# DS144-1_0-B.net
KiCad netlist of a schematic drawn in Altium Designer
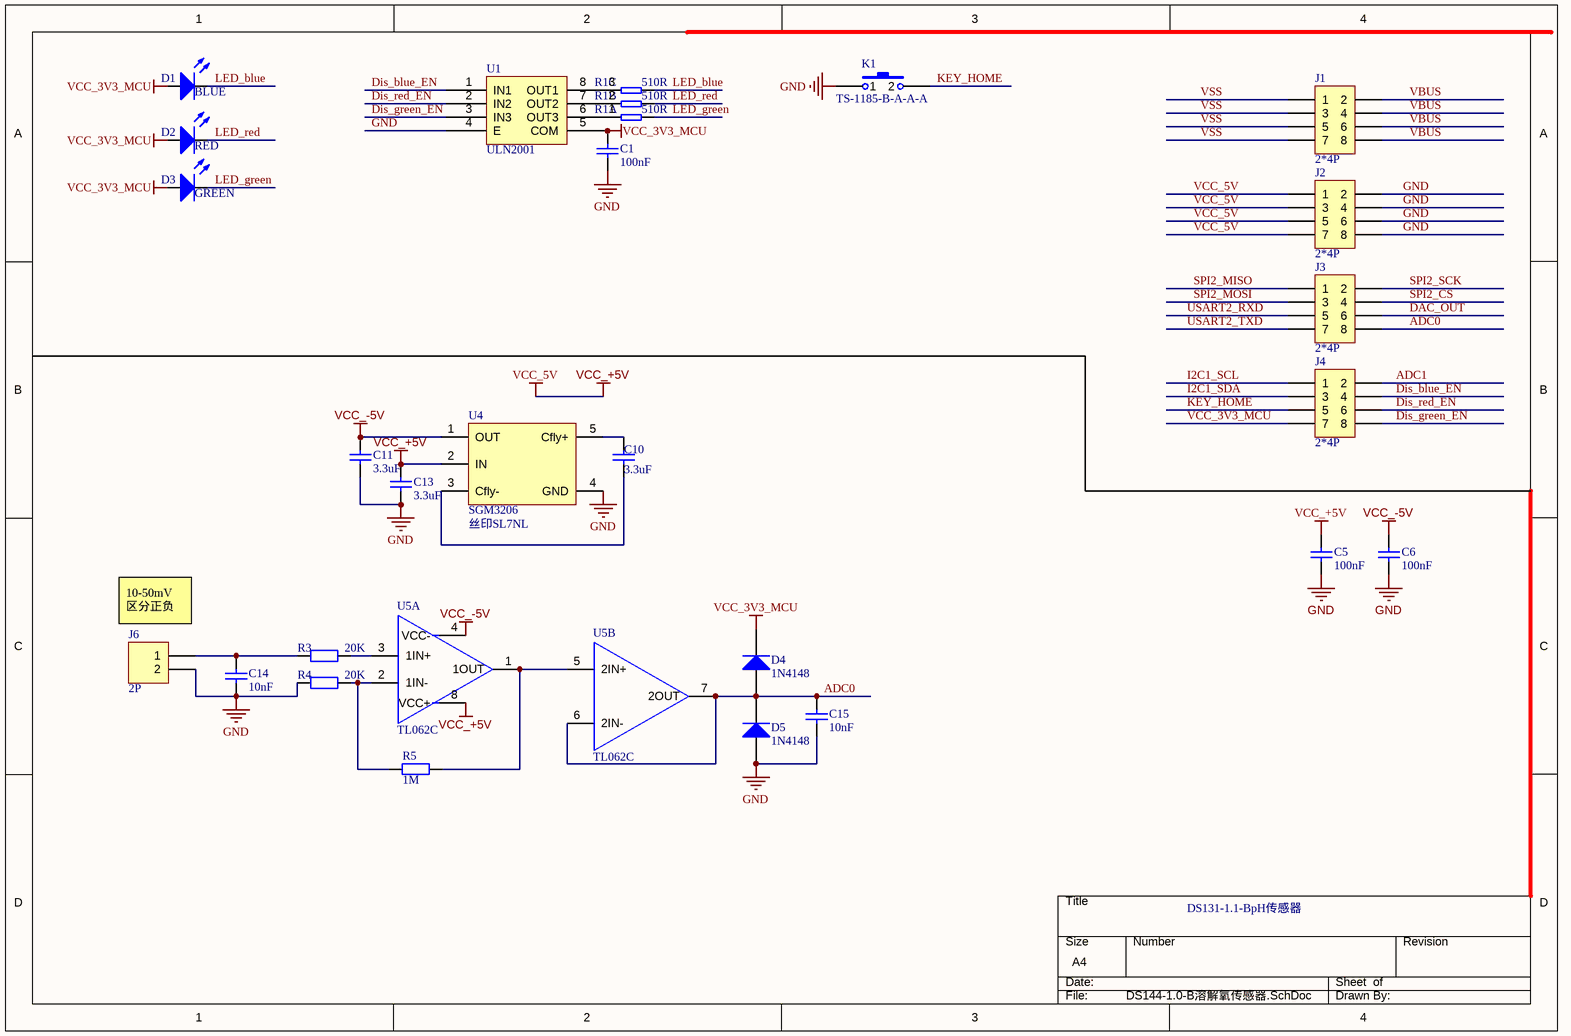
[diagram p0: DS144-1.0-B溶解氧传感器.SchDoc]

(export (version "E")
  (design (tool "Eeschema 10.0.6"))
  (components
    (comp (ref "C1")
      (value "100nF")
      (footprint "0603CAP")
      (description "贴片电容")
      (fields (field (name "Comment") "SMDCAP00013"))
      (libsource (lib "AD_SCH") (part "MLCC 100nF 50V ±10％ 0603"))
    )
    (comp (ref "C5")
      (value "100nF")
      (footprint "0603CAP")
      (description "贴片电容")
      (fields (field (name "Comment") "SMDCAP00013"))
      (libsource (lib "AD_SCH") (part "MLCC 100nF 50V ±10％ 0603"))
    )
    (comp (ref "C6")
      (value "100nF")
      (footprint "0603CAP")
      (description "贴片电容")
      (fields (field (name "Comment") "SMDCAP00013"))
      (libsource (lib "AD_SCH") (part "MLCC 100nF 50V ±10％ 0603"))
    )
    (comp (ref "C10")
      (value "3.3uF")
      (footprint "0603CAP")
      (description "贴片电容")
      (fields (field (name "Comment") "SMDCAP00016"))
      (libsource (lib "AD_SCH") (part "MLCC 10uF 50V ±10％ 0603"))
    )
    (comp (ref "C11")
      (value "3.3uF")
      (footprint "0603CAP")
      (description "贴片电容")
      (fields (field (name "Comment") "SMDCAP00016"))
      (libsource (lib "AD_SCH") (part "MLCC 10uF 50V ±10％ 0603"))
    )
    (comp (ref "C13")
      (value "3.3uF")
      (footprint "0603CAP")
      (description "贴片电容")
      (fields (field (name "Comment") "SMDCAP00016"))
      (libsource (lib "AD_SCH") (part "MLCC 10uF 50V ±10％ 0603"))
    )
    (comp (ref "C14")
      (value "10nF")
      (footprint "0603CAP")
      (description "贴片电容")
      (fields (field (name "Comment") "SMDCAP00010"))
      (libsource (lib "AD_SCH") (part "MLCC 10nF 50V ±10％ 0603"))
    )
    (comp (ref "C15")
      (value "10nF")
      (footprint "0603CAP")
      (description "贴片电容")
      (fields (field (name "Comment") "SMDCAP00010"))
      (libsource (lib "AD_SCH") (part "MLCC 10nF 50V ±10％ 0603"))
    )
    (comp (ref "D1")
      (value "BLUE")
      (footprint "LED_0805")
      (description "贴片LED")
      (fields (field (name "Comment") "SMDLED00010"))
      (libsource (lib "AD_SCH") (part "Chip 蓝色LED 0805"))
    )
    (comp (ref "D2")
      (value "RED")
      (footprint "LED_0805")
      (description "贴片LED")
      (fields (field (name "Comment") "SMDLED00003"))
      (libsource (lib "AD_SCH") (part "Chip 红色LED 0805"))
    )
    (comp (ref "D3")
      (value "GREEN")
      (footprint "LED_0805")
      (description "贴片LED")
      (fields (field (name "Comment") "Chip 翠绿LED 0805"))
      (libsource (lib "AD_SCH") (part "Chip 翠绿LED 0805"))
    )
    (comp (ref "D4")
      (value "1N4148")
      (footprint "SOD-123")
      (description "贴片开关二极管 T4")
      (fields (field (name "Comment") "DIPDIODE02001"))
      (libsource (lib "AD_SCH") (part "1N4148W"))
    )
    (comp (ref "D5")
      (value "1N4148")
      (footprint "SOD-123")
      (description "贴片开关二极管 T4")
      (fields (field (name "Comment") "DIPDIODE02001"))
      (libsource (lib "AD_SCH") (part "1N4148W"))
    )
    (comp (ref "J1")
      (value "2*4P")
      (footprint "X1321WVS-2x04J-C40D53")
      (description "双排针2x4P 立贴 1.27mm")
      (fields (field (name "Comment") "X1321WVS-2x04J-C40D53"))
      (libsource (lib "AD_SCH") (part "X1321WVS-2x04J-C40D53"))
    )
    (comp (ref "J2")
      (value "2*4P")
      (footprint "X1321WVS-2x04J-C40D53")
      (description "双排针2x4P 立贴 1.27mm")
      (fields (field (name "Comment") "X1321WVS-2x04J-C40D53"))
      (libsource (lib "AD_SCH") (part "X1321WVS-2x04J-C40D53"))
    )
    (comp (ref "J3")
      (value "2*4P")
      (footprint "X1321WVS-2x04J-C40D53")
      (description "双排针2x4P 立贴 1.27mm")
      (fields (field (name "Comment") "X1321WVS-2x04J-C40D53"))
      (libsource (lib "AD_SCH") (part "X1321WVS-2x04J-C40D53"))
    )
    (comp (ref "J4")
      (value "2*4P")
      (footprint "X1321WVS-2x04J-C40D53")
      (description "双排针2x4P 立贴 1.27mm")
      (fields (field (name "Comment") "X1321WVS-2x04J-C40D53"))
      (libsource (lib "AD_SCH") (part "X1321WVS-2x04J-C40D53"))
    )
    (comp (ref "J6")
      (value "2P")
      (footprint "SIP2")
      (description "单排直针")
      (fields (field (name "Comment") "SL000000042"))
      (libsource (lib "AD_SCH") (part "DIP2 单排直针 1*40P 间距2.54mm 针长11mm 铜"))
    )
    (comp (ref "K1")
      (value "TS-1185-B-A-A-A")
      (footprint "KEY_TS-1185-x-A-A-A")
      (description "轻触开关")
      (libsource (lib "AD_SCH") (part "TS-1185-B-A-A-A"))
    )
    (comp (ref "R1")
      (value "510R")
      (footprint "0603RES_Pack4")
      (description "贴片排阻")
      (fields (field (name "Comment") "SMDRES05003"))
      (libsource (lib "AD_SCH") (part "Chip R*4 510R 1/16W ±5％ 0603"))
    )
    (comp (ref "R3")
      (value "20K")
      (footprint "0603RES")
      (description "贴片电阻")
      (fields (field (name "Comment") "SMDRES00058"))
      (libsource (lib "") (part "Chip 20K 1/16W ±1％ 0603_1"))
    )
    (comp (ref "R4")
      (value "20K")
      (footprint "0603RES")
      (description "贴片电阻")
      (fields (field (name "Comment") "SMDRES00058"))
      (libsource (lib "AD_SCH") (part "Chip 20K 1/16W ±1％ 0603"))
    )
    (comp (ref "R5")
      (value "1M")
      (footprint "0603RES")
      (description "贴片电阻")
      (fields (field (name "Comment") "SMDRES00085"))
      (libsource (lib "AD_SCH") (part "Chip 1M 1/16W ±1％ 0603"))
    )
    (comp (ref "U1")
      (value "ULN2001")
      (footprint "SO-8")
      (description "电机驱动芯片")
      (fields (field (name "Comment") "SMDIC000018"))
      (libsource (lib "AD_SCH") (part "ULN2001 SOP-8"))
    )
    (comp (ref "U4")
      (value "SGM3206")
      (footprint "SOT23-5")
      (description "电荷泵芯片")
      (fields (field (name "ALTIUM_VALUE") "丝印SL7NL"))
      (libsource (lib "AD_SCH") (part "SGM3206"))
    )
    (comp (ref "U5") (value "TL062C") (footprint "SO-8") (libsource (lib "AD_SCH") (part "TL062C")))
  )
  (nets
    (net (code "1") (name "/ADC0") (class "Default")
      (node (ref "C15") (pin "2") (pinfunction "2_2") (pintype "passive"))
      (node (ref "D4") (pin "1") (pinfunction "A_1") (pintype "passive"))
      (node (ref "D5") (pin "2") (pinfunction "K_2") (pintype "passive"))
      (node (ref "J3") (pin "8") (pinfunction "8_8") (pintype "passive"))
      (node (ref "U5") (pin "6") (pinfunction "2IN-_6") (pintype "passive"))
      (node (ref "U5") (pin "7") (pinfunction "2OUT_7") (pintype "passive"))
    )
    (net (code "2") (name "/ADC1") (class "Default")
      (node (ref "J4") (pin "2") (pinfunction "2_2") (pintype "passive"))
    )
    (net (code "3") (name "/DAC_OUT") (class "Default")
      (node (ref "J3") (pin "6") (pinfunction "6_6") (pintype "passive"))
    )
    (net (code "4") (name "/Dis_blue_EN") (class "Default")
      (node (ref "J4") (pin "4") (pinfunction "4_4") (pintype "passive"))
      (node (ref "U1") (pin "1") (pinfunction "IN1_1") (pintype "passive"))
    )
    (net (code "5") (name "/Dis_green_EN") (class "Default")
      (node (ref "J4") (pin "8") (pinfunction "8_8") (pintype "passive"))
      (node (ref "U1") (pin "3") (pinfunction "IN3_3") (pintype "passive"))
    )
    (net (code "6") (name "/Dis_red_EN") (class "Default")
      (node (ref "J4") (pin "6") (pinfunction "6_6") (pintype "passive"))
      (node (ref "U1") (pin "2") (pinfunction "IN2_2") (pintype "passive"))
    )
    (net (code "7") (name "/I2C1_SCL") (class "Default")
      (node (ref "J4") (pin "1") (pinfunction "1_1") (pintype "passive"))
    )
    (net (code "8") (name "/I2C1_SDA") (class "Default")
      (node (ref "J4") (pin "3") (pinfunction "3_3") (pintype "passive"))
    )
    (net (code "9") (name "/KEY_HOME") (class "Default")
      (node (ref "J4") (pin "5") (pinfunction "5_5") (pintype "passive"))
      (node (ref "K1") (pin "2") (pinfunction "2_2") (pintype "passive"))
    )
    (net (code "10") (name "/LED_blue") (class "Default")
      (node (ref "D1") (pin "2") (pinfunction "K_2") (pintype "passive"))
      (node (ref "R1") (pin "6") (pinfunction "6_6") (pintype "passive"))
    )
    (net (code "11") (name "/LED_green") (class "Default")
      (node (ref "D3") (pin "2") (pinfunction "K_2") (pintype "passive"))
      (node (ref "R1") (pin "8") (pinfunction "8_8") (pintype "passive"))
    )
    (net (code "12") (name "/LED_red") (class "Default")
      (node (ref "D2") (pin "2") (pinfunction "K_2") (pintype "passive"))
      (node (ref "R1") (pin "7") (pinfunction "7_7") (pintype "passive"))
    )
    (net (code "13") (name "/SPI2_CS") (class "Default")
      (node (ref "J3") (pin "4") (pinfunction "4_4") (pintype "passive"))
    )
    (net (code "14") (name "/SPI2_MISO") (class "Default")
      (node (ref "J3") (pin "1") (pinfunction "1_1") (pintype "passive"))
    )
    (net (code "15") (name "/SPI2_MOSI") (class "Default")
      (node (ref "J3") (pin "3") (pinfunction "3_3") (pintype "passive"))
    )
    (net (code "16") (name "/SPI2_SCK") (class "Default")
      (node (ref "J3") (pin "2") (pinfunction "2_2") (pintype "passive"))
    )
    (net (code "17") (name "/USART2_RXD") (class "Default")
      (node (ref "J3") (pin "5") (pinfunction "5_5") (pintype "passive"))
    )
    (net (code "18") (name "/USART2_TXD") (class "Default")
      (node (ref "J3") (pin "7") (pinfunction "7_7") (pintype "passive"))
    )
    (net (code "19") (name "/VBUS") (class "Default")
      (node (ref "J1") (pin "2") (pinfunction "2_2") (pintype "passive"))
      (node (ref "J1") (pin "4") (pinfunction "4_4") (pintype "passive"))
      (node (ref "J1") (pin "6") (pinfunction "6_6") (pintype "passive"))
      (node (ref "J1") (pin "8") (pinfunction "8_8") (pintype "passive"))
    )
    (net (code "20") (name "/VSS") (class "Default")
      (node (ref "J1") (pin "1") (pinfunction "1_1") (pintype "passive"))
      (node (ref "J1") (pin "3") (pinfunction "3_3") (pintype "passive"))
      (node (ref "J1") (pin "5") (pinfunction "5_5") (pintype "passive"))
      (node (ref "J1") (pin "7") (pinfunction "7_7") (pintype "passive"))
    )
    (net (code "21") (name "GND") (class "Default")
      (node (ref "C1") (pin "1") (pinfunction "1_1") (pintype "passive"))
      (node (ref "C11") (pin "2") (pinfunction "2_2") (pintype "passive"))
      (node (ref "C13") (pin "2") (pinfunction "2_2") (pintype "passive"))
      (node (ref "C14") (pin "1") (pinfunction "1_1") (pintype "passive"))
      (node (ref "C15") (pin "1") (pinfunction "1_1") (pintype "passive"))
      (node (ref "C5") (pin "1") (pinfunction "1_1") (pintype "passive"))
      (node (ref "C6") (pin "1") (pinfunction "1_1") (pintype "passive"))
      (node (ref "D5") (pin "1") (pinfunction "A_1") (pintype "passive"))
      (node (ref "J2") (pin "2") (pinfunction "2_2") (pintype "passive"))
      (node (ref "J2") (pin "4") (pinfunction "4_4") (pintype "passive"))
      (node (ref "J2") (pin "6") (pinfunction "6_6") (pintype "passive"))
      (node (ref "J2") (pin "8") (pinfunction "8_8") (pintype "passive"))
      (node (ref "J6") (pin "2") (pinfunction "2_2") (pintype "passive"))
      (node (ref "K1") (pin "1") (pinfunction "1_1") (pintype "passive"))
      (node (ref "R4") (pin "1") (pinfunction "1_1") (pintype "passive"))
      (node (ref "U1") (pin "4") (pinfunction "E_4") (pintype "passive"))
      (node (ref "U4") (pin "4") (pinfunction "GND_4") (pintype "passive"))
    )
    (net (code "22") (name "Net-(C14-Pad2)") (class "Default")
      (node (ref "C14") (pin "2") (pinfunction "2_2") (pintype "passive"))
      (node (ref "J6") (pin "1") (pinfunction "1_1") (pintype "passive"))
      (node (ref "R3") (pin "2") (pinfunction "2_2") (pintype "passive"))
    )
    (net (code "23") (name "Net-(U1-OUT1)") (class "Default")
      (node (ref "R1") (pin "3") (pinfunction "3_3") (pintype "passive"))
      (node (ref "U1") (pin "8") (pinfunction "OUT1_8") (pintype "passive"))
    )
    (net (code "24") (name "Net-(U1-OUT2)") (class "Default")
      (node (ref "R1") (pin "2") (pinfunction "2_2") (pintype "passive"))
      (node (ref "U1") (pin "7") (pinfunction "OUT2_7") (pintype "passive"))
    )
    (net (code "25") (name "Net-(U1-OUT3)") (class "Default")
      (node (ref "R1") (pin "1") (pinfunction "1_1") (pintype "passive"))
      (node (ref "U1") (pin "6") (pinfunction "OUT3_6") (pintype "passive"))
    )
    (net (code "26") (name "Net-(U4-Cfly+)") (class "Default")
      (node (ref "C10") (pin "2") (pinfunction "2_2") (pintype "passive"))
      (node (ref "U4") (pin "5") (pinfunction "Cfly+_5") (pintype "passive"))
    )
    (net (code "27") (name "Net-(U4-Cfly-)") (class "Default")
      (node (ref "C10") (pin "1") (pinfunction "1_1") (pintype "passive"))
      (node (ref "U4") (pin "3") (pinfunction "Cfly-_3") (pintype "passive"))
    )
    (net (code "28") (name "Net-(U5A-1IN+)") (class "Default")
      (node (ref "R3") (pin "1") (pinfunction "1_1") (pintype "passive"))
      (node (ref "U5") (pin "3") (pinfunction "1IN+_3") (pintype "passive"))
    )
    (net (code "29") (name "Net-(U5A-1IN-)") (class "Default")
      (node (ref "R4") (pin "2") (pinfunction "2_2") (pintype "passive"))
      (node (ref "R5") (pin "1") (pinfunction "1_1") (pintype "passive"))
      (node (ref "U5") (pin "2") (pinfunction "1IN-_2") (pintype "passive"))
    )
    (net (code "30") (name "Net-(U5A-1OUT)") (class "Default")
      (node (ref "R5") (pin "2") (pinfunction "2_2") (pintype "passive"))
      (node (ref "U5") (pin "1") (pinfunction "1OUT_1") (pintype "passive"))
      (node (ref "U5") (pin "5") (pinfunction "2IN+_5") (pintype "passive"))
    )
    (net (code "31") (name "VCC_+5V") (class "Default")
      (node (ref "C13") (pin "1") (pinfunction "1_1") (pintype "passive"))
      (node (ref "C5") (pin "2") (pinfunction "2_2") (pintype "passive"))
      (node (ref "J2") (pin "1") (pinfunction "1_1") (pintype "passive"))
      (node (ref "J2") (pin "3") (pinfunction "3_3") (pintype "passive"))
      (node (ref "J2") (pin "5") (pinfunction "5_5") (pintype "passive"))
      (node (ref "J2") (pin "7") (pinfunction "7_7") (pintype "passive"))
      (node (ref "U4") (pin "2") (pinfunction "IN_2") (pintype "passive"))
      (node (ref "U5") (pin "8") (pinfunction "VCC+_8") (pintype "passive"))
    )
    (net (code "32") (name "VCC_-5V") (class "Default")
      (node (ref "C11") (pin "1") (pinfunction "1_1") (pintype "passive"))
      (node (ref "C6") (pin "2") (pinfunction "2_2") (pintype "passive"))
      (node (ref "U4") (pin "1") (pinfunction "OUT_1") (pintype "passive"))
      (node (ref "U5") (pin "4") (pinfunction "VCC-_4") (pintype "passive"))
    )
    (net (code "33") (name "VCC_3V3_MCU") (class "Default")
      (node (ref "C1") (pin "2") (pinfunction "2_2") (pintype "passive"))
      (node (ref "D1") (pin "1") (pinfunction "A_1") (pintype "passive"))
      (node (ref "D2") (pin "1") (pinfunction "A_1") (pintype "passive"))
      (node (ref "D3") (pin "1") (pinfunction "A_1") (pintype "passive"))
      (node (ref "D4") (pin "2") (pinfunction "K_2") (pintype "passive"))
      (node (ref "J4") (pin "7") (pinfunction "7_7") (pintype "passive"))
      (node (ref "U1") (pin "5") (pinfunction "COM_5") (pintype "passive"))
    )
  )
)
